# SCHEMATIC_FILE_ARDUINO_UNO.net
KiCad netlist of a schematic drawn in EAGLE
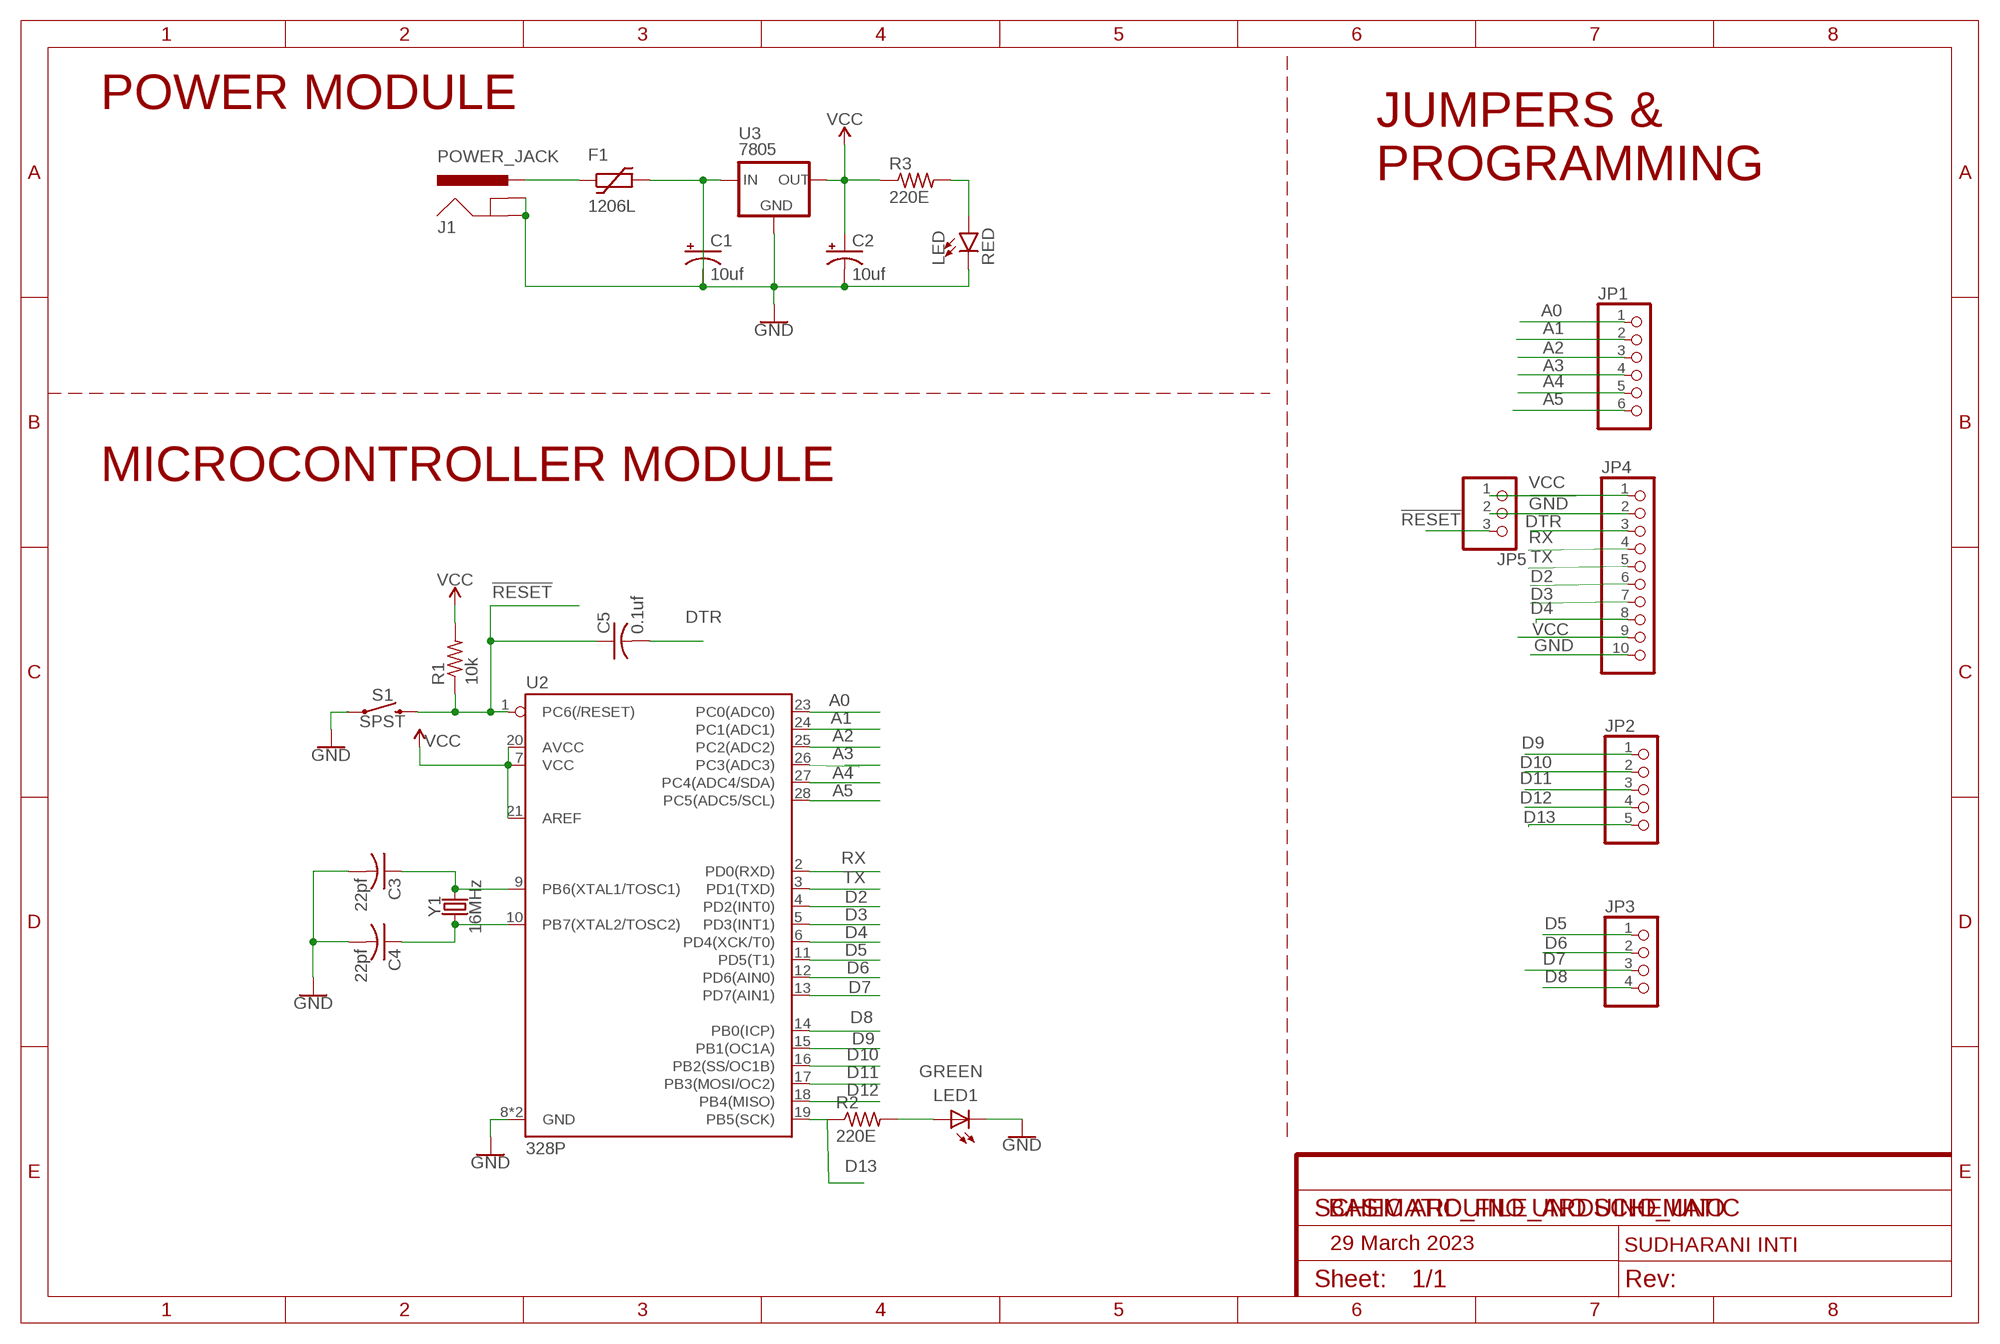
[diagram p0: schematic, sheet 1]

(export (version "E")
  (design (tool "Eeschema 10.0.6"))
  (components
    (comp (ref "C1")
      (value "10uf")
      (footprint "eagle-import:E2,5-6E")
      (libsource (lib "eagle-import") (part "CPOL-USE2,5-6E"))
    )
    (comp (ref "C2")
      (value "10uf")
      (footprint "eagle-import:E2,5-6E")
      (libsource (lib "eagle-import") (part "CPOL-USE2,5-6E"))
    )
    (comp (ref "C3")
      (value "22pf")
      (footprint "eagle-import:C025-024X044")
      (libsource (lib "eagle-import") (part "C-US025-024X044"))
    )
    (comp (ref "C4")
      (value "22pf")
      (footprint "eagle-import:C025-024X044")
      (libsource (lib "eagle-import") (part "C-US025-024X044"))
    )
    (comp (ref "C5")
      (value "0.1uf")
      (footprint "eagle-import:C025-024X044")
      (libsource (lib "eagle-import") (part "C-US025-024X044"))
    )
    (comp (ref "F1")
      (value "1206L")
      (footprint "eagle-import:1206L")
      (libsource (lib "eagle-import") (part "1206L"))
    )
    (comp (ref "J1")
      (value "POWER_JACK")
      (footprint "eagle-import:POWER_JACK_PTH")
      (libsource (lib "eagle-import") (part "POWER_JACK"))
    )
    (comp (ref "JP1")
      (value "PINHD-1X6")
      (footprint "eagle-import:1X06")
      (libsource (lib "eagle-import") (part "PINHD-1X6"))
    )
    (comp (ref "JP2")
      (value "PINHD-1X5")
      (footprint "eagle-import:1X05")
      (libsource (lib "eagle-import") (part "PINHD-1X5"))
    )
    (comp (ref "JP3")
      (value "PINHD-1X4")
      (footprint "eagle-import:1X04")
      (libsource (lib "eagle-import") (part "PINHD-1X4"))
    )
    (comp (ref "JP4")
      (value "PINHD-1X10")
      (footprint "eagle-import:1X10")
      (libsource (lib "eagle-import") (part "PINHD-1X10"))
    )
    (comp (ref "JP5")
      (value "PINHD-1X3")
      (footprint "eagle-import:1X03")
      (libsource (lib "eagle-import") (part "PINHD-1X3"))
    )
    (comp (ref "LED")
      (value "RED")
      (footprint "eagle-import:LED_3MM")
      (libsource (lib "eagle-import") (part "LED3MM"))
    )
    (comp (ref "LED1")
      (value "GREEN")
      (footprint "eagle-import:LED3MM")
      (libsource (lib "eagle-import") (part "adafruit_LED3MM"))
    )
    (comp (ref "R1")
      (value "10k")
      (footprint "eagle-import:0204_7")
      (libsource (lib "eagle-import") (part "R-US_0204/7"))
    )
    (comp (ref "R2")
      (value "220E")
      (footprint "eagle-import:0204_7")
      (libsource (lib "eagle-import") (part "R-US_0204/7"))
    )
    (comp (ref "R3")
      (value "220E")
      (footprint "eagle-import:0204_7")
      (libsource (lib "eagle-import") (part "R-US_0204/7"))
    )
    (comp (ref "S1")
      (value "SPST")
      (footprint "eagle-import:TACTILE_SWITCH_PTH_6.0MM")
      (libsource (lib "eagle-import") (part "MOMENTARY-SWITCH-SPST-PTH-6.0MM"))
    )
    (comp (ref "U2")
      (value "328P")
      (footprint "eagle-import:DIP28")
      (libsource (lib "eagle-import") (part "ATMEGA328P_PDIP"))
    )
    (comp (ref "U3")
      (value "7805")
      (footprint "eagle-import:78XXS")
      (libsource (lib "eagle-import") (part "78XXS"))
    )
    (comp (ref "Y1")
      (value "16MHz")
      (footprint "eagle-import:HC49US")
      (libsource (lib "eagle-import") (part "CRYSTAL-16MHZPTH-HC49US"))
    )
  )
  (nets
    (net (code "1") (name "/A0") (class "Default")
      (node (ref "JP1") (pin "1") (pinfunction "1_1") (pintype "passive"))
      (node (ref "U2") (pin "23") (pinfunction "PC0(ADC0)_23") (pintype "bidirectional"))
    )
    (net (code "2") (name "/A1") (class "Default")
      (node (ref "JP1") (pin "2") (pinfunction "2_2") (pintype "passive"))
      (node (ref "U2") (pin "24") (pinfunction "PC1(ADC1)_24") (pintype "bidirectional"))
    )
    (net (code "3") (name "/A2") (class "Default")
      (node (ref "JP1") (pin "3") (pinfunction "3_3") (pintype "passive"))
      (node (ref "U2") (pin "25") (pinfunction "PC2(ADC2)_25") (pintype "bidirectional"))
    )
    (net (code "4") (name "/A3") (class "Default")
      (node (ref "JP1") (pin "4") (pinfunction "4_4") (pintype "passive"))
      (node (ref "U2") (pin "26") (pinfunction "PC3(ADC3)_26") (pintype "bidirectional"))
    )
    (net (code "5") (name "/A4") (class "Default")
      (node (ref "JP1") (pin "5") (pinfunction "5_5") (pintype "passive"))
      (node (ref "U2") (pin "27") (pinfunction "PC4(ADC4/SDA)_27") (pintype "bidirectional"))
    )
    (net (code "6") (name "/A5") (class "Default")
      (node (ref "JP1") (pin "6") (pinfunction "6_6") (pintype "passive"))
      (node (ref "U2") (pin "28") (pinfunction "PC5(ADC5/SCL)_28") (pintype "bidirectional"))
    )
    (net (code "7") (name "/D2") (class "Default")
      (node (ref "JP4") (pin "6") (pinfunction "6_6") (pintype "passive"))
      (node (ref "U2") (pin "4") (pinfunction "PD2(INT0)_4") (pintype "bidirectional"))
    )
    (net (code "8") (name "/D3") (class "Default")
      (node (ref "JP4") (pin "7") (pinfunction "7_7") (pintype "passive"))
      (node (ref "U2") (pin "5") (pinfunction "PD3(INT1)_5") (pintype "bidirectional"))
    )
    (net (code "9") (name "/D4") (class "Default")
      (node (ref "JP4") (pin "8") (pinfunction "8_8") (pintype "passive"))
      (node (ref "U2") (pin "6") (pinfunction "PD4(XCK/T0)_6") (pintype "bidirectional"))
    )
    (net (code "10") (name "/D5") (class "Default")
      (node (ref "JP3") (pin "1") (pinfunction "1_1") (pintype "passive"))
      (node (ref "U2") (pin "11") (pinfunction "PD5(T1)_11") (pintype "bidirectional"))
    )
    (net (code "11") (name "/D6") (class "Default")
      (node (ref "JP3") (pin "2") (pinfunction "2_2") (pintype "passive"))
      (node (ref "U2") (pin "12") (pinfunction "PD6(AIN0)_12") (pintype "bidirectional"))
    )
    (net (code "12") (name "/D7") (class "Default")
      (node (ref "JP3") (pin "3") (pinfunction "3_3") (pintype "passive"))
      (node (ref "U2") (pin "13") (pinfunction "PD7(AIN1)_13") (pintype "bidirectional"))
    )
    (net (code "13") (name "/D8") (class "Default")
      (node (ref "JP3") (pin "4") (pinfunction "4_4") (pintype "passive"))
      (node (ref "U2") (pin "14") (pinfunction "PB0(ICP)_14") (pintype "bidirectional"))
    )
    (net (code "14") (name "/D9") (class "Default")
      (node (ref "JP2") (pin "1") (pinfunction "1_1") (pintype "passive"))
      (node (ref "U2") (pin "15") (pinfunction "PB1(OC1A)_15") (pintype "bidirectional"))
    )
    (net (code "15") (name "/D10") (class "Default")
      (node (ref "JP2") (pin "2") (pinfunction "2_2") (pintype "passive"))
      (node (ref "U2") (pin "16") (pinfunction "PB2(SS/OC1B)_16") (pintype "bidirectional"))
    )
    (net (code "16") (name "/D11") (class "Default")
      (node (ref "JP2") (pin "3") (pinfunction "3_3") (pintype "passive"))
      (node (ref "U2") (pin "17") (pinfunction "PB3(MOSI/OC2)_17") (pintype "bidirectional"))
    )
    (net (code "17") (name "/D12") (class "Default")
      (node (ref "JP2") (pin "4") (pinfunction "4_4") (pintype "passive"))
      (node (ref "U2") (pin "18") (pinfunction "PB4(MISO)_18") (pintype "bidirectional"))
    )
    (net (code "18") (name "/D13") (class "Default")
      (node (ref "JP2") (pin "5") (pinfunction "5_5") (pintype "passive"))
      (node (ref "R2") (pin "1") (pinfunction "1_1") (pintype "passive"))
      (node (ref "U2") (pin "19") (pinfunction "PB5(SCK)_19") (pintype "bidirectional"))
    )
    (net (code "19") (name "/DTR") (class "Default")
      (node (ref "C5") (pin "2") (pinfunction "2_2") (pintype "passive"))
      (node (ref "JP4") (pin "3") (pinfunction "3_3") (pintype "passive"))
    )
    (net (code "20") (name "/RX") (class "Default")
      (node (ref "JP4") (pin "4") (pinfunction "4_4") (pintype "passive"))
      (node (ref "U2") (pin "2") (pinfunction "PD0(RXD)_2") (pintype "bidirectional"))
    )
    (net (code "21") (name "/TX") (class "Default")
      (node (ref "JP4") (pin "5") (pinfunction "5_5") (pintype "passive"))
      (node (ref "U2") (pin "3") (pinfunction "PD1(TXD)_3") (pintype "bidirectional"))
    )
    (net (code "22") (name "/~{RESET}") (class "Default")
      (node (ref "C5") (pin "1") (pinfunction "1_1") (pintype "passive"))
      (node (ref "JP5") (pin "3") (pinfunction "3_3") (pintype "passive"))
      (node (ref "R1") (pin "1") (pinfunction "1_1") (pintype "passive"))
      (node (ref "S1") (pin "3") (pinfunction "2_3") (pintype "passive"))
      (node (ref "U2") (pin "1") (pinfunction "PC6(/RESET)_1") (pintype "bidirectional"))
    )
    (net (code "23") (name "GND") (class "Default")
      (node (ref "C1") (pin "-") (pinfunction "-_-") (pintype "passive"))
      (node (ref "C2") (pin "-") (pinfunction "-_-") (pintype "passive"))
      (node (ref "C3") (pin "2") (pinfunction "2_2") (pintype "passive"))
      (node (ref "C4") (pin "2") (pinfunction "2_2") (pintype "passive"))
      (node (ref "J1") (pin "GND") (pinfunction "GND_GND") (pintype "bidirectional"))
      (node (ref "J1") (pin "GNDBREAK") (pinfunction "GNDBREAK_GNDBREAK") (pintype "bidirectional"))
      (node (ref "JP4") (pin "10") (pinfunction "10_10") (pintype "passive"))
      (node (ref "JP4") (pin "2") (pinfunction "2_2") (pintype "passive"))
      (node (ref "JP5") (pin "2") (pinfunction "2_2") (pintype "passive"))
      (node (ref "LED") (pin "K") (pinfunction "C_K") (pintype "passive"))
      (node (ref "LED1") (pin "K") (pinfunction "C_K") (pintype "passive"))
      (node (ref "S1") (pin "1") (pinfunction "1_1") (pintype "passive"))
      (node (ref "U2") (pin "22") (pinfunction "GND_22") (pintype "bidirectional"))
      (node (ref "U2") (pin "8") (pinfunction "GND_8") (pintype "bidirectional"))
      (node (ref "U3") (pin "GND") (pinfunction "GND_GND") (pintype "input"))
    )
    (net (code "24") (name "Net-(F1-1)") (class "Default")
      (node (ref "F1") (pin "P$1") (pinfunction "1_P$1") (pintype "passive"))
      (node (ref "J1") (pin "PWR") (pinfunction "PWR_PWR") (pintype "bidirectional"))
    )
    (net (code "25") (name "Net-(F1-2)") (class "Default")
      (node (ref "C1") (pin "+") (pinfunction "+_+") (pintype "passive"))
      (node (ref "F1") (pin "P$2") (pinfunction "2_P$2") (pintype "passive"))
      (node (ref "U3") (pin "IN") (pinfunction "IN_IN") (pintype "input"))
    )
    (net (code "26") (name "Net-(LED-PadA)") (class "Default")
      (node (ref "LED") (pin "A") (pinfunction "A_A") (pintype "passive"))
      (node (ref "R3") (pin "2") (pinfunction "2_2") (pintype "passive"))
    )
    (net (code "27") (name "Net-(LED1-PadA)") (class "Default")
      (node (ref "LED1") (pin "A") (pinfunction "A_A") (pintype "passive"))
      (node (ref "R2") (pin "2") (pinfunction "2_2") (pintype "passive"))
    )
    (net (code "28") (name "Net-(U2-PB6(XTAL1{slash}TOSC1))") (class "Default")
      (node (ref "C3") (pin "1") (pinfunction "1_1") (pintype "passive"))
      (node (ref "U2") (pin "9") (pinfunction "PB6(XTAL1/TOSC1)_9") (pintype "bidirectional"))
      (node (ref "Y1") (pin "2") (pinfunction "2_2") (pintype "passive"))
    )
    (net (code "29") (name "Net-(U2-PB7(XTAL2{slash}TOSC2))") (class "Default")
      (node (ref "C4") (pin "1") (pinfunction "1_1") (pintype "passive"))
      (node (ref "U2") (pin "10") (pinfunction "PB7(XTAL2/TOSC2)_10") (pintype "bidirectional"))
      (node (ref "Y1") (pin "1") (pinfunction "1_1") (pintype "passive"))
    )
    (net (code "30") (name "VCC") (class "Default")
      (node (ref "C2") (pin "+") (pinfunction "+_+") (pintype "passive"))
      (node (ref "JP4") (pin "1") (pinfunction "1_1") (pintype "passive"))
      (node (ref "JP4") (pin "9") (pinfunction "9_9") (pintype "passive"))
      (node (ref "JP5") (pin "1") (pinfunction "1_1") (pintype "passive"))
      (node (ref "R1") (pin "2") (pinfunction "2_2") (pintype "passive"))
      (node (ref "R3") (pin "1") (pinfunction "1_1") (pintype "passive"))
      (node (ref "U2") (pin "20") (pinfunction "AVCC_20") (pintype "bidirectional"))
      (node (ref "U2") (pin "21") (pinfunction "AREF_21") (pintype "bidirectional"))
      (node (ref "U2") (pin "7") (pinfunction "VCC_7") (pintype "bidirectional"))
      (node (ref "U3") (pin "OUT") (pinfunction "OUT_OUT") (pintype "passive"))
    )
  )
)
